# PowerSupply.net
KiCad netlist of a schematic drawn in Altium Designer
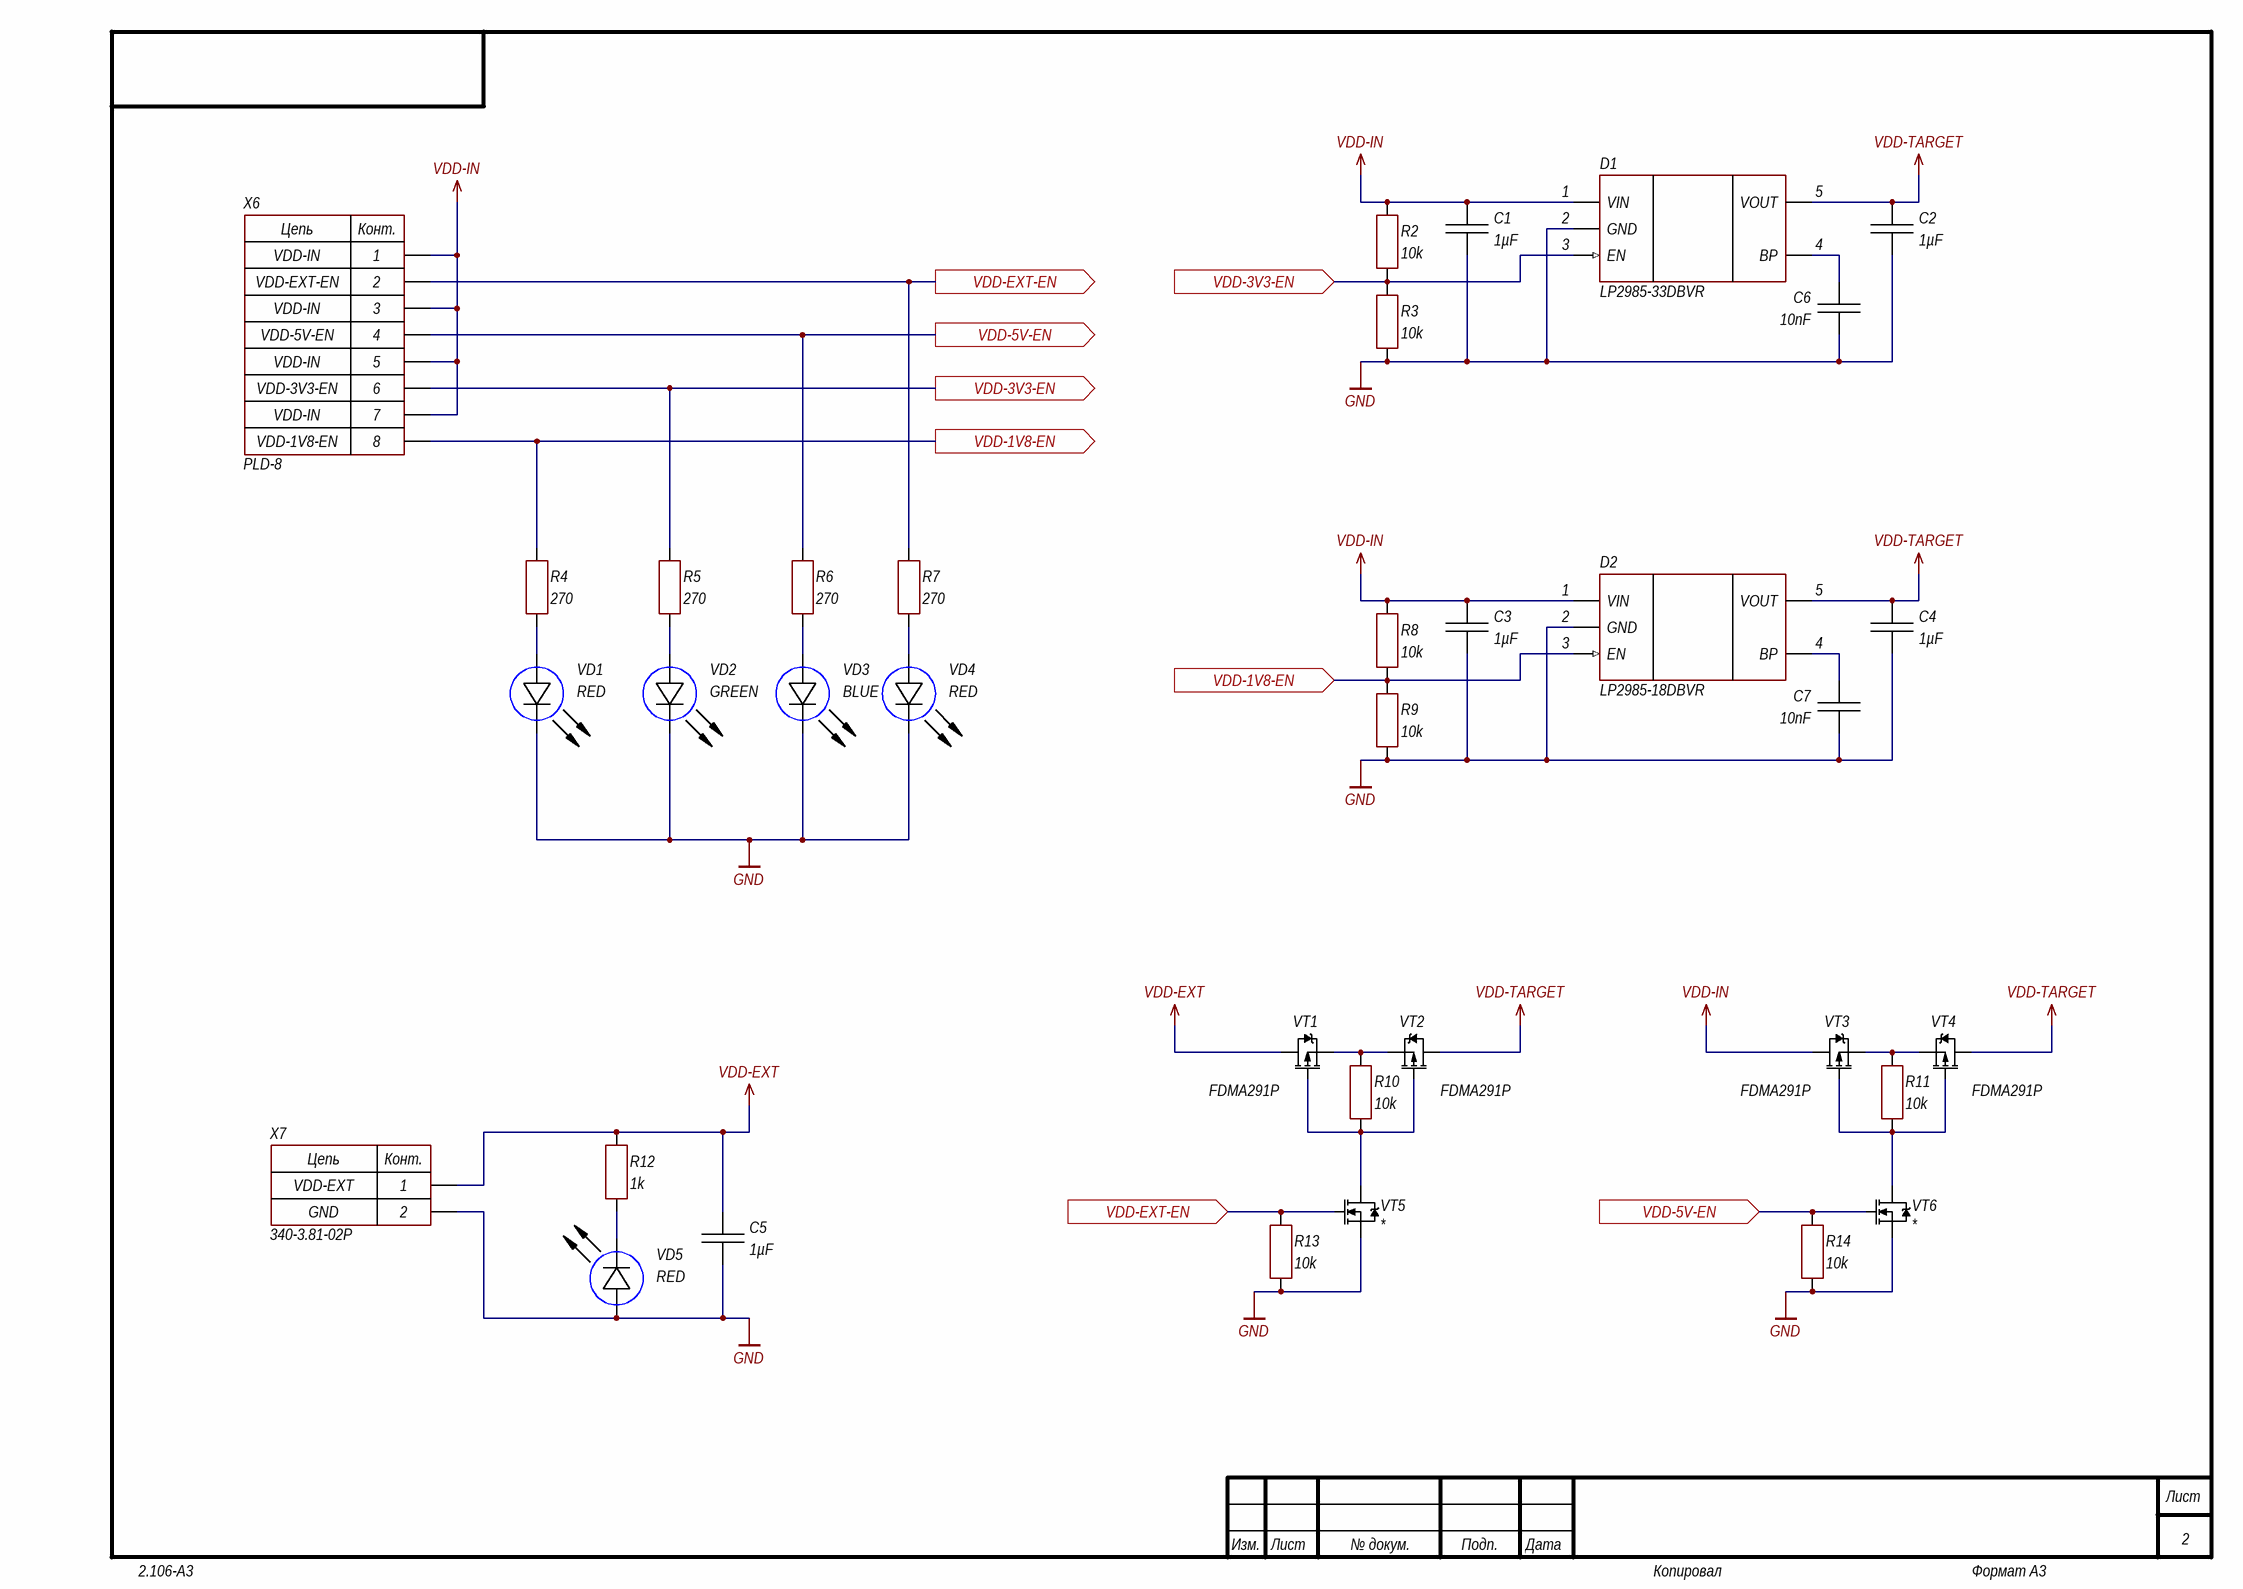
[diagram p0: PowerSupply.SchDoc]

(export (version "E")
  (design (tool "Eeschema 10.0.6"))
  (components
    (comp (ref "C1") (value "1µF") (footprint "CH0603CM") (libsource (lib "Discrete") (part "Capacitor")))
    (comp (ref "C2") (value "1µF") (footprint "CH0603CM") (libsource (lib "Discrete") (part "Capacitor")))
    (comp (ref "C3") (value "1µF") (footprint "CH0603CM") (libsource (lib "Discrete") (part "Capacitor")))
    (comp (ref "C4") (value "1µF") (footprint "CH0603CM") (libsource (lib "Discrete") (part "Capacitor")))
    (comp (ref "C5") (value "1µF") (footprint "CH0603CM") (libsource (lib "Discrete") (part "Capacitor")))
    (comp (ref "C6") (value "10nF") (footprint "CH0603CM") (libsource (lib "Discrete") (part "Capacitor")))
    (comp (ref "C7") (value "10nF") (footprint "CH0603CM") (libsource (lib "Discrete") (part "Capacitor")))
    (comp (ref "D1")
      (value "LP2985-33DBVR")
      (footprint "SOT23-5")
      (description "LDO")
      (fields (field (name "MANUFACTURER") "Texas Instruments"))
      (libsource (lib "Power Supplies") (part "LP2985-33DBVR"))
    )
    (comp (ref "D2")
      (value "LP2985-18DBVR")
      (footprint "SOT23-5")
      (description "LDO")
      (fields (field (name "MANUFACTURER") "Texas Instruments"))
      (libsource (lib "Power Supplies") (part "LP2985-33DBVR"))
    )
    (comp (ref "R2") (value "10k") (footprint "CH0402R") (libsource (lib "Discrete") (part "Resistor")))
    (comp (ref "R3") (value "10k") (footprint "CH0402R") (libsource (lib "Discrete") (part "Resistor")))
    (comp (ref "R4") (value "270") (footprint "CH0402R") (libsource (lib "Discrete") (part "Resistor")))
    (comp (ref "R5") (value "270") (footprint "CH0402R") (libsource (lib "Discrete") (part "Resistor")))
    (comp (ref "R6") (value "270") (footprint "CH0402R") (libsource (lib "Discrete") (part "Resistor")))
    (comp (ref "R7") (value "270") (footprint "CH0402R") (libsource (lib "Discrete") (part "Resistor")))
    (comp (ref "R8") (value "10k") (footprint "CH0402R") (libsource (lib "Discrete") (part "Resistor")))
    (comp (ref "R9") (value "10k") (footprint "CH0402R") (libsource (lib "Discrete") (part "Resistor")))
    (comp (ref "R10") (value "10k") (footprint "CH0402R") (libsource (lib "Discrete") (part "Resistor")))
    (comp (ref "R11") (value "10k") (footprint "CH0402R") (libsource (lib "Discrete") (part "Resistor")))
    (comp (ref "R12") (value "1k") (footprint "CH0402R") (libsource (lib "Discrete") (part "Resistor")))
    (comp (ref "R13") (value "10k") (footprint "CH0402R") (libsource (lib "Discrete") (part "Resistor")))
    (comp (ref "R14") (value "10k") (footprint "CH0402R") (libsource (lib "Discrete") (part "Resistor")))
    (comp (ref "VD1") (value "RED") (footprint "CH0402LR") (libsource (lib "Discrete") (part "LED")))
    (comp (ref "VD2") (value "GREEN") (footprint "CH0402LG") (libsource (lib "Discrete") (part "LED")))
    (comp (ref "VD3") (value "BLUE") (footprint "CH0402LB") (libsource (lib "Discrete") (part "LED")))
    (comp (ref "VD4") (value "RED") (footprint "CH0402LR") (libsource (lib "Discrete") (part "LED")))
    (comp (ref "VD5") (value "RED") (footprint "CH0402LR") (libsource (lib "Discrete") (part "LED")))
    (comp (ref "VT1")
      (value "FDMA291P")
      (footprint "MicroFET 2x2")
      (description "Mosfet")
      (libsource (lib "Transistor") (part "P-chanel"))
    )
    (comp (ref "VT2")
      (value "FDMA291P")
      (footprint "MicroFET 2x2")
      (description "Mosfet")
      (libsource (lib "Transistor") (part "P-chanel"))
    )
    (comp (ref "VT3")
      (value "FDMA291P")
      (footprint "MicroFET 2x2")
      (description "Mosfet")
      (libsource (lib "Transistor") (part "P-chanel"))
    )
    (comp (ref "VT4")
      (value "FDMA291P")
      (footprint "MicroFET 2x2")
      (description "Mosfet")
      (libsource (lib "Transistor") (part "P-chanel"))
    )
    (comp (ref "VT5")
      (value "*")
      (footprint "DFN1006-3L")
      (description "Mosfet")
      (libsource (lib "Transistor") (part "N-chanel"))
    )
    (comp (ref "VT6")
      (value "*")
      (footprint "DFN1006-3L")
      (description "Mosfet")
      (libsource (lib "Transistor") (part "N-chanel"))
    )
    (comp (ref "X6")
      (value "PLD-8")
      (footprint "CON: PLD-8")
      (libsource (lib "Connectors") (part "8-Connector"))
    )
    (comp (ref "X7")
      (value "340-3.81-02P")
      (footprint "CON: 340-3.81-02P")
      (libsource (lib "Connectors") (part "2-Connector"))
    )
  )
  (nets
    (net (code "1") (name "/VDD-1V8-EN") (class "Default")
      (node (ref "D2") (pin "3") (pinfunction "EN_3") (pintype "input"))
      (node (ref "R4") (pin "2") (pinfunction "2_2") (pintype "passive"))
      (node (ref "R8") (pin "1") (pinfunction "1_1") (pintype "passive"))
      (node (ref "R9") (pin "2") (pinfunction "2_2") (pintype "passive"))
      (node (ref "X6") (pin "8") (pinfunction "8_8") (pintype "passive"))
    )
    (net (code "2") (name "/VDD-3V3-EN") (class "Default")
      (node (ref "D1") (pin "3") (pinfunction "EN_3") (pintype "input"))
      (node (ref "R2") (pin "1") (pinfunction "1_1") (pintype "passive"))
      (node (ref "R3") (pin "2") (pinfunction "2_2") (pintype "passive"))
      (node (ref "R5") (pin "2") (pinfunction "2_2") (pintype "passive"))
      (node (ref "X6") (pin "6") (pinfunction "6_6") (pintype "passive"))
    )
    (net (code "3") (name "/VDD-5V-EN") (class "Default")
      (node (ref "R14") (pin "2") (pinfunction "2_2") (pintype "passive"))
      (node (ref "R6") (pin "2") (pinfunction "2_2") (pintype "passive"))
      (node (ref "VT6") (pin "1") (pinfunction "G_1") (pintype "passive"))
      (node (ref "X6") (pin "4") (pinfunction "4_4") (pintype "passive"))
    )
    (net (code "4") (name "/VDD-EXT-EN") (class "Default")
      (node (ref "R13") (pin "2") (pinfunction "2_2") (pintype "passive"))
      (node (ref "R7") (pin "2") (pinfunction "2_2") (pintype "passive"))
      (node (ref "VT5") (pin "1") (pinfunction "G_1") (pintype "passive"))
      (node (ref "X6") (pin "2") (pinfunction "2_2") (pintype "passive"))
    )
    (net (code "5") (name "GND") (class "Default")
      (node (ref "C1") (pin "1") (pinfunction "1_1") (pintype "passive"))
      (node (ref "C2") (pin "1") (pinfunction "1_1") (pintype "passive"))
      (node (ref "C3") (pin "1") (pinfunction "1_1") (pintype "passive"))
      (node (ref "C4") (pin "1") (pinfunction "1_1") (pintype "passive"))
      (node (ref "C5") (pin "1") (pinfunction "1_1") (pintype "passive"))
      (node (ref "C6") (pin "1") (pinfunction "1_1") (pintype "passive"))
      (node (ref "C7") (pin "1") (pinfunction "1_1") (pintype "passive"))
      (node (ref "D1") (pin "2") (pinfunction "GND_2") (pintype "passive"))
      (node (ref "D2") (pin "2") (pinfunction "GND_2") (pintype "passive"))
      (node (ref "R13") (pin "1") (pinfunction "1_1") (pintype "passive"))
      (node (ref "R14") (pin "1") (pinfunction "1_1") (pintype "passive"))
      (node (ref "R3") (pin "1") (pinfunction "1_1") (pintype "passive"))
      (node (ref "R9") (pin "1") (pinfunction "1_1") (pintype "passive"))
      (node (ref "VD1") (pin "2") (pinfunction "C_2") (pintype "passive"))
      (node (ref "VD2") (pin "2") (pinfunction "C_2") (pintype "passive"))
      (node (ref "VD3") (pin "2") (pinfunction "C_2") (pintype "passive"))
      (node (ref "VD4") (pin "2") (pinfunction "C_2") (pintype "passive"))
      (node (ref "VD5") (pin "1") (pinfunction "A_1") (pintype "passive"))
      (node (ref "VT5") (pin "3") (pinfunction "S_3") (pintype "passive"))
      (node (ref "VT6") (pin "3") (pinfunction "S_3") (pintype "passive"))
      (node (ref "X7") (pin "2") (pinfunction "2_2") (pintype "passive"))
    )
    (net (code "6") (name "Net-(D1-BP)") (class "Default")
      (node (ref "C6") (pin "2") (pinfunction "2_2") (pintype "passive"))
      (node (ref "D1") (pin "4") (pinfunction "BP_4") (pintype "passive"))
    )
    (net (code "7") (name "Net-(D2-BP)") (class "Default")
      (node (ref "C7") (pin "2") (pinfunction "2_2") (pintype "passive"))
      (node (ref "D2") (pin "4") (pinfunction "BP_4") (pintype "passive"))
    )
    (net (code "8") (name "Net-(VD1-A)") (class "Default")
      (node (ref "R4") (pin "1") (pinfunction "1_1") (pintype "passive"))
      (node (ref "VD1") (pin "1") (pinfunction "A_1") (pintype "passive"))
    )
    (net (code "9") (name "Net-(VD2-A)") (class "Default")
      (node (ref "R5") (pin "1") (pinfunction "1_1") (pintype "passive"))
      (node (ref "VD2") (pin "1") (pinfunction "A_1") (pintype "passive"))
    )
    (net (code "10") (name "Net-(VD3-A)") (class "Default")
      (node (ref "R6") (pin "1") (pinfunction "1_1") (pintype "passive"))
      (node (ref "VD3") (pin "1") (pinfunction "A_1") (pintype "passive"))
    )
    (net (code "11") (name "Net-(VD4-A)") (class "Default")
      (node (ref "R7") (pin "1") (pinfunction "1_1") (pintype "passive"))
      (node (ref "VD4") (pin "1") (pinfunction "A_1") (pintype "passive"))
    )
    (net (code "12") (name "Net-(VD5-C)") (class "Default")
      (node (ref "R12") (pin "1") (pinfunction "1_1") (pintype "passive"))
      (node (ref "VD5") (pin "2") (pinfunction "C_2") (pintype "passive"))
    )
    (net (code "13") (name "Net-(VT1-G)") (class "Default")
      (node (ref "R10") (pin "1") (pinfunction "1_1") (pintype "passive"))
      (node (ref "VT1") (pin "1") (pinfunction "G_1") (pintype "passive"))
      (node (ref "VT2") (pin "1") (pinfunction "G_1") (pintype "passive"))
      (node (ref "VT5") (pin "2") (pinfunction "D_2") (pintype "passive"))
    )
    (net (code "14") (name "Net-(VT1-S)") (class "Default")
      (node (ref "R10") (pin "2") (pinfunction "2_2") (pintype "passive"))
      (node (ref "VT1") (pin "3") (pinfunction "S_3") (pintype "passive"))
      (node (ref "VT2") (pin "3") (pinfunction "S_3") (pintype "passive"))
    )
    (net (code "15") (name "Net-(VT3-G)") (class "Default")
      (node (ref "R11") (pin "1") (pinfunction "1_1") (pintype "passive"))
      (node (ref "VT3") (pin "1") (pinfunction "G_1") (pintype "passive"))
      (node (ref "VT4") (pin "1") (pinfunction "G_1") (pintype "passive"))
      (node (ref "VT6") (pin "2") (pinfunction "D_2") (pintype "passive"))
    )
    (net (code "16") (name "Net-(VT3-S)") (class "Default")
      (node (ref "R11") (pin "2") (pinfunction "2_2") (pintype "passive"))
      (node (ref "VT3") (pin "3") (pinfunction "S_3") (pintype "passive"))
      (node (ref "VT4") (pin "3") (pinfunction "S_3") (pintype "passive"))
    )
    (net (code "17") (name "VDD-EXT") (class "Default")
      (node (ref "C5") (pin "2") (pinfunction "2_2") (pintype "passive"))
      (node (ref "R12") (pin "2") (pinfunction "2_2") (pintype "passive"))
      (node (ref "VT1") (pin "2") (pinfunction "D_2") (pintype "passive"))
      (node (ref "X7") (pin "1") (pinfunction "1_1") (pintype "passive"))
    )
    (net (code "18") (name "VDD-IN") (class "Default")
      (node (ref "C1") (pin "2") (pinfunction "2_2") (pintype "passive"))
      (node (ref "C3") (pin "2") (pinfunction "2_2") (pintype "passive"))
      (node (ref "D1") (pin "1") (pinfunction "VIN_1") (pintype "passive"))
      (node (ref "D2") (pin "1") (pinfunction "VIN_1") (pintype "passive"))
      (node (ref "R2") (pin "2") (pinfunction "2_2") (pintype "passive"))
      (node (ref "R8") (pin "2") (pinfunction "2_2") (pintype "passive"))
      (node (ref "VT3") (pin "2") (pinfunction "D_2") (pintype "passive"))
      (node (ref "X6") (pin "1") (pinfunction "1_1") (pintype "passive"))
      (node (ref "X6") (pin "3") (pinfunction "3_3") (pintype "passive"))
      (node (ref "X6") (pin "5") (pinfunction "5_5") (pintype "passive"))
      (node (ref "X6") (pin "7") (pinfunction "7_7") (pintype "passive"))
    )
    (net (code "19") (name "VDD-TARGET") (class "Default")
      (node (ref "C2") (pin "2") (pinfunction "2_2") (pintype "passive"))
      (node (ref "C4") (pin "2") (pinfunction "2_2") (pintype "passive"))
      (node (ref "D1") (pin "5") (pinfunction "VOUT_5") (pintype "passive"))
      (node (ref "D2") (pin "5") (pinfunction "VOUT_5") (pintype "passive"))
      (node (ref "VT2") (pin "2") (pinfunction "D_2") (pintype "passive"))
      (node (ref "VT4") (pin "2") (pinfunction "D_2") (pintype "passive"))
    )
  )
)
